# POE_V3.net
KiCad netlist of a schematic drawn in EAGLE
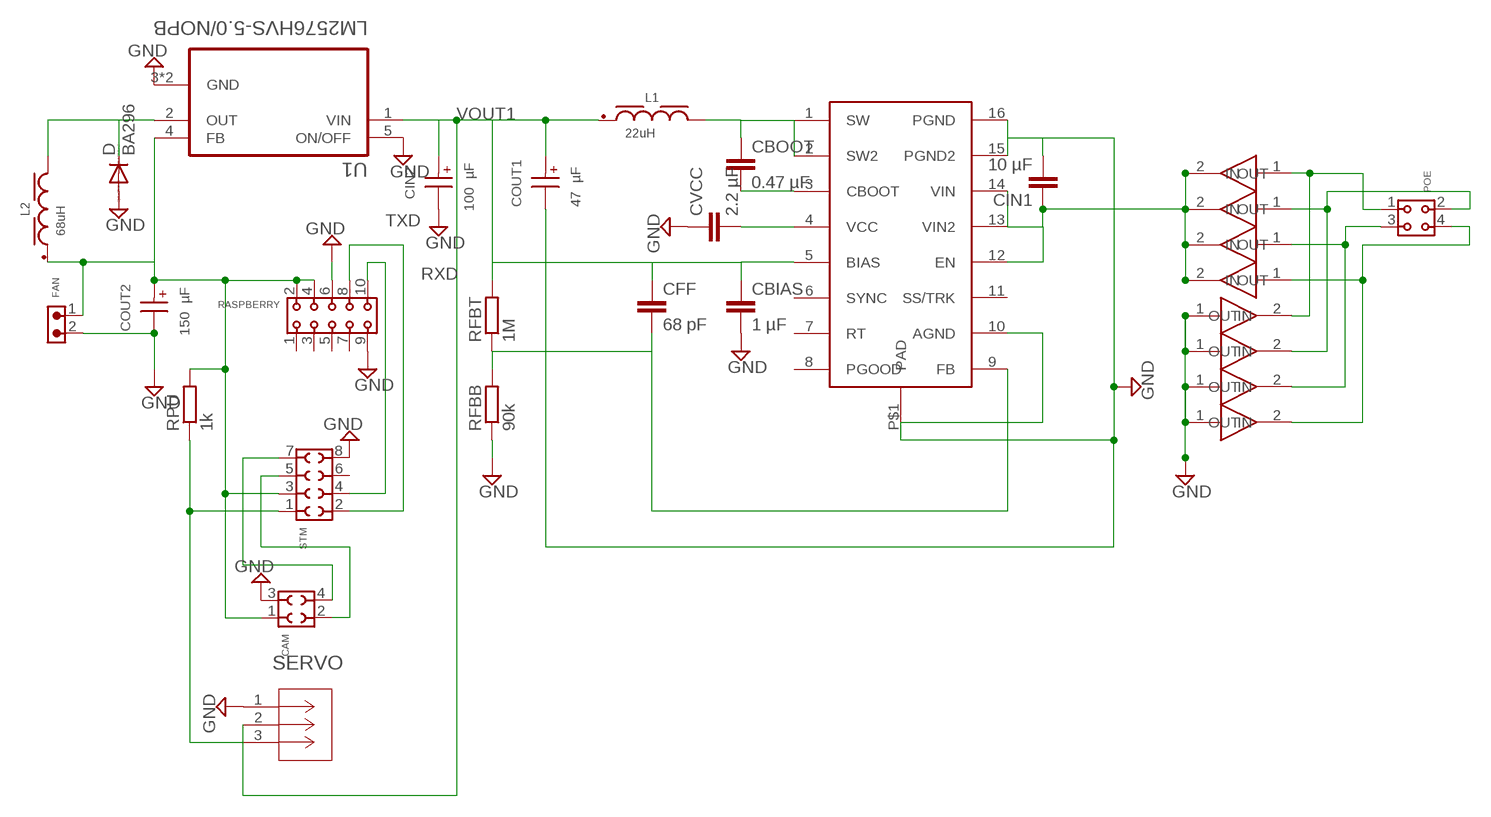
[diagram p0: schematic, sheet 1]

(export (version "E")
  (design (tool "Eeschema 10.0.6"))
  (components
    (comp (ref "CAM")
      (value "6100XX21821_61000421821")
      (footprint "eagle-import:61000421821")
      (libsource (lib "eagle-import") (part "6100XX21821_61000421821"))
    )
    (comp (ref "CBIAS")
      (value "1 µF")
      (footprint "eagle-import:C1206")
      (libsource (lib "eagle-import") (part "C-EUC1206"))
    )
    (comp (ref "CBOOT")
      (value "0.47 µF")
      (footprint "eagle-import:C1206")
      (libsource (lib "eagle-import") (part "C-EUC1206"))
    )
    (comp (ref "CFF")
      (value "68 pF")
      (footprint "eagle-import:C1206")
      (libsource (lib "eagle-import") (part "C-EUC1206"))
    )
    (comp (ref "CIN1")
      (value "10 µF")
      (footprint "eagle-import:C2220K")
      (libsource (lib "eagle-import") (part "rcl_334_C-EUC2220K"))
    )
    (comp (ref "CIN2")
      (value "100 µF")
      (footprint "eagle-import:WCAP-ASLI_6.3X5.5(DXL)")
      (libsource (lib "eagle-import") (part "WCAP-ASLI_6.3X5.5_865080343009"))
    )
    (comp (ref "COUT1")
      (value "47 µF")
      (footprint "eagle-import:WCAP-ASLI_5X5.5(DXL)")
      (libsource (lib "eagle-import") (part "WCAP-ASLI_5X5.5_865080342006"))
    )
    (comp (ref "COUT2")
      (value "150 µF")
      (footprint "eagle-import:WCAP-ASLI_6.3X5.5(DXL)")
      (libsource (lib "eagle-import") (part "WCAP-ASLI_6.3X5.5_865080143008"))
    )
    (comp (ref "CVCC")
      (value "2.2 µF")
      (footprint "eagle-import:C1206")
      (libsource (lib "eagle-import") (part "C-EUC1206"))
    )
    (comp (ref "D")
      (value "BA296")
      (footprint "eagle-import:P2-15")
      (libsource (lib "eagle-import") (part "BA296"))
    )
    (comp (ref "FAN")
      (value "6130XX11021_61300211021")
      (footprint "eagle-import:61300211021")
      (libsource (lib "eagle-import") (part "6130XX11021_61300211021"))
    )
    (comp (ref "L1")
      (value "22uH")
      (footprint "eagle-import:WE-PD_1260")
      (libsource (lib "eagle-import") (part "WE-PD_1260_744771122"))
    )
    (comp (ref "L2")
      (value "68uH")
      (footprint "eagle-import:WE-PD_1210")
      (libsource (lib "eagle-import") (part "WE-PD_1210_7447709680"))
    )
    (comp (ref "POE")
      (value "6130XX21821_61300421821")
      (footprint "eagle-import:61300421821")
      (libsource (lib "eagle-import") (part "6130XX21821_61300421821"))
    )
    (comp (ref "RASPBERRY")
      (value "6130XX21821_61301021821")
      (footprint "eagle-import:61301021821")
      (libsource (lib "eagle-import") (part "6130XX21821_61301021821"))
    )
    (comp (ref "RFBB")
      (value "90k")
      (footprint "eagle-import:M1206")
      (libsource (lib "eagle-import") (part "R-EU_M1206"))
    )
    (comp (ref "RFBT")
      (value "1M")
      (footprint "eagle-import:M1206")
      (libsource (lib "eagle-import") (part "R-EU_M1206"))
    )
    (comp (ref "RPU")
      (value "1k")
      (footprint "eagle-import:M1206")
      (libsource (lib "eagle-import") (part "R-EU_M1206"))
    )
    (comp (ref "SERVO")
      (value "22035035")
      (footprint "eagle-import:CON_22035035")
      (fields (field (name "COPYRIGHT") "Copyright (C) 2018 Accelerated Designs. All rights reserved"))
      (libsource (lib "eagle-import") (part "22035035"))
    )
    (comp (ref "STM")
      (value "6100XX21821_61000821821")
      (footprint "eagle-import:61000821821")
      (libsource (lib "eagle-import") (part "6100XX21821_61000821821"))
    )
    (comp (ref "U$1")
      (value "LM46002")
      (footprint "eagle-import:TSSOP16")
      (libsource (lib "eagle-import") (part "LM46002"))
    )
    (comp (ref "U$2")
      (value "RGF1D")
      (footprint "eagle-import:RGF1D")
      (libsource (lib "eagle-import") (part "RGF1D"))
    )
    (comp (ref "U$3")
      (value "RGF1D")
      (footprint "eagle-import:RGF1D")
      (libsource (lib "eagle-import") (part "RGF1D"))
    )
    (comp (ref "U$4")
      (value "RGF1D")
      (footprint "eagle-import:RGF1D")
      (libsource (lib "eagle-import") (part "RGF1D"))
    )
    (comp (ref "U$5")
      (value "RGF1D")
      (footprint "eagle-import:RGF1D")
      (libsource (lib "eagle-import") (part "RGF1D"))
    )
    (comp (ref "U$6")
      (value "RGF1D")
      (footprint "eagle-import:RGF1D")
      (libsource (lib "eagle-import") (part "RGF1D"))
    )
    (comp (ref "U$7")
      (value "RGF1D")
      (footprint "eagle-import:RGF1D")
      (libsource (lib "eagle-import") (part "RGF1D"))
    )
    (comp (ref "U$8")
      (value "RGF1D")
      (footprint "eagle-import:RGF1D")
      (libsource (lib "eagle-import") (part "RGF1D"))
    )
    (comp (ref "U$9")
      (value "RGF1D")
      (footprint "eagle-import:RGF1D")
      (libsource (lib "eagle-import") (part "RGF1D"))
    )
    (comp (ref "U1")
      (value "LM2576HVS-5.0/NOPB")
      (footprint "eagle-import:VREG_TPS79625KTTR")
      (fields
        (field (name "DIGI-KEY_PART_NUMBER") "LM2576HVS-5.0/NOPB-ND")
        (field (name "MF") "Texas Instruments")
      )
      (libsource (lib "eagle-import") (part "LM2576HVS-5.0/NOPB"))
    )
  )
  (nets
    (net (code "1") (name "/RXD") (class "Default")
      (node (ref "RASPBERRY") (pin "10") (pinfunction "10_10") (pintype "passive"))
      (node (ref "STM") (pin "4") (pinfunction "4_4") (pintype "passive"))
    )
    (net (code "2") (name "/TXD") (class "Default")
      (node (ref "RASPBERRY") (pin "8") (pinfunction "8_8") (pintype "passive"))
      (node (ref "STM") (pin "2") (pinfunction "2_2") (pintype "passive"))
    )
    (net (code "3") (name "/VOUT1") (class "Default")
      (node (ref "CBIAS") (pin "1") (pinfunction "1_1") (pintype "passive"))
      (node (ref "CFF") (pin "1") (pinfunction "1_1") (pintype "passive"))
      (node (ref "CIN2") (pin "1") (pinfunction "+_1") (pintype "passive"))
      (node (ref "COUT1") (pin "1") (pinfunction "+_1") (pintype "passive"))
      (node (ref "L1") (pin "1") (pinfunction "1_1") (pintype "passive"))
      (node (ref "RFBT") (pin "2") (pinfunction "2_2") (pintype "passive"))
      (node (ref "SERVO") (pin "2") (pinfunction "2_2") (pintype "passive"))
      (node (ref "U$1") (pin "5") (pinfunction "BIAS_5") (pintype "bidirectional"))
      (node (ref "U1") (pin "1") (pinfunction "VIN_1") (pintype "input"))
    )
    (net (code "4") (name "GND") (class "Default")
      (node (ref "CAM") (pin "3") (pinfunction "3_3") (pintype "passive"))
      (node (ref "CBIAS") (pin "2") (pinfunction "2_2") (pintype "passive"))
      (node (ref "CIN1") (pin "2") (pinfunction "2_2") (pintype "passive"))
      (node (ref "CIN2") (pin "2") (pinfunction "-_2") (pintype "passive"))
      (node (ref "COUT1") (pin "2") (pinfunction "-_2") (pintype "passive"))
      (node (ref "COUT2") (pin "2") (pinfunction "-_2") (pintype "passive"))
      (node (ref "CVCC") (pin "1") (pinfunction "1_1") (pintype "passive"))
      (node (ref "D") (pin "A") (pinfunction "A_A") (pintype "passive"))
      (node (ref "FAN") (pin "2") (pinfunction "2_2") (pintype "passive"))
      (node (ref "RASPBERRY") (pin "6") (pinfunction "6_6") (pintype "passive"))
      (node (ref "RASPBERRY") (pin "9") (pinfunction "9_9") (pintype "passive"))
      (node (ref "RFBB") (pin "1") (pinfunction "1_1") (pintype "passive"))
      (node (ref "SERVO") (pin "1") (pinfunction "1_1") (pintype "passive"))
      (node (ref "STM") (pin "8") (pinfunction "8_8") (pintype "passive"))
      (node (ref "U$1") (pin "10") (pinfunction "AGND_10") (pintype "bidirectional"))
      (node (ref "U$1") (pin "15") (pinfunction "PGND2_15") (pintype "bidirectional"))
      (node (ref "U$1") (pin "16") (pinfunction "PGND_16") (pintype "bidirectional"))
      (node (ref "U$1") (pin "P$1") (pinfunction "PAD_P$1") (pintype "bidirectional"))
      (node (ref "U$4") (pin "1") (pinfunction "IN_1") (pintype "bidirectional"))
      (node (ref "U$5") (pin "1") (pinfunction "IN_1") (pintype "bidirectional"))
      (node (ref "U$8") (pin "1") (pinfunction "IN_1") (pintype "bidirectional"))
      (node (ref "U$9") (pin "1") (pinfunction "IN_1") (pintype "bidirectional"))
      (node (ref "U1") (pin "3") (pinfunction "GND_3") (pintype "power_in"))
      (node (ref "U1") (pin "5") (pinfunction "ON/OFF_5") (pintype "input"))
      (node (ref "U1") (pin "6") (pinfunction "GND_6") (pintype "power_in"))
    )
    (net (code "5") (name "Net-(CAM-Pad2)") (class "Default")
      (node (ref "CAM") (pin "2") (pinfunction "2_2") (pintype "passive"))
      (node (ref "STM") (pin "5") (pinfunction "5_5") (pintype "passive"))
    )
    (net (code "6") (name "Net-(CAM-Pad4)") (class "Default")
      (node (ref "CAM") (pin "4") (pinfunction "4_4") (pintype "passive"))
      (node (ref "STM") (pin "7") (pinfunction "7_7") (pintype "passive"))
    )
    (net (code "7") (name "Net-(COUT2-+)") (class "Default")
      (node (ref "CAM") (pin "1") (pinfunction "1_1") (pintype "passive"))
      (node (ref "COUT2") (pin "1") (pinfunction "+_1") (pintype "passive"))
      (node (ref "FAN") (pin "1") (pinfunction "1_1") (pintype "passive"))
      (node (ref "L2") (pin "1") (pinfunction "1_1") (pintype "passive"))
      (node (ref "RASPBERRY") (pin "2") (pinfunction "2_2") (pintype "passive"))
      (node (ref "RASPBERRY") (pin "4") (pinfunction "4_4") (pintype "passive"))
      (node (ref "RPU") (pin "2") (pinfunction "2_2") (pintype "passive"))
      (node (ref "STM") (pin "3") (pinfunction "3_3") (pintype "passive"))
      (node (ref "U1") (pin "4") (pinfunction "FB_4") (pintype "output"))
    )
    (net (code "8") (name "Net-(RPU-Pad1)") (class "Default")
      (node (ref "RPU") (pin "1") (pinfunction "1_1") (pintype "passive"))
      (node (ref "SERVO") (pin "3") (pinfunction "3_3") (pintype "passive"))
      (node (ref "STM") (pin "1") (pinfunction "1_1") (pintype "passive"))
    )
    (net (code "9") (name "Net-(U$1-CBOOT)") (class "Default")
      (node (ref "CBOOT") (pin "2") (pinfunction "2_2") (pintype "passive"))
      (node (ref "U$1") (pin "3") (pinfunction "CBOOT_3") (pintype "bidirectional"))
    )
    (net (code "10") (name "Net-(U$1-EN)") (class "Default")
      (node (ref "CIN1") (pin "1") (pinfunction "1_1") (pintype "passive"))
      (node (ref "U$1") (pin "12") (pinfunction "EN_12") (pintype "bidirectional"))
      (node (ref "U$1") (pin "13") (pinfunction "VIN2_13") (pintype "bidirectional"))
      (node (ref "U$1") (pin "14") (pinfunction "VIN_14") (pintype "bidirectional"))
      (node (ref "U$2") (pin "2") (pinfunction "OUT_2") (pintype "bidirectional"))
      (node (ref "U$3") (pin "2") (pinfunction "OUT_2") (pintype "bidirectional"))
      (node (ref "U$6") (pin "2") (pinfunction "OUT_2") (pintype "bidirectional"))
      (node (ref "U$7") (pin "2") (pinfunction "OUT_2") (pintype "bidirectional"))
    )
    (net (code "11") (name "Net-(U$1-FB)") (class "Default")
      (node (ref "CFF") (pin "2") (pinfunction "2_2") (pintype "passive"))
      (node (ref "RFBB") (pin "2") (pinfunction "2_2") (pintype "passive"))
      (node (ref "RFBT") (pin "1") (pinfunction "1_1") (pintype "passive"))
      (node (ref "U$1") (pin "9") (pinfunction "FB_9") (pintype "bidirectional"))
    )
    (net (code "12") (name "Net-(U$1-SW)") (class "Default")
      (node (ref "CBOOT") (pin "1") (pinfunction "1_1") (pintype "passive"))
      (node (ref "L1") (pin "2") (pinfunction "2_2") (pintype "passive"))
      (node (ref "U$1") (pin "1") (pinfunction "SW_1") (pintype "bidirectional"))
      (node (ref "U$1") (pin "2") (pinfunction "SW2_2") (pintype "bidirectional"))
    )
    (net (code "13") (name "Net-(U$1-VCC)") (class "Default")
      (node (ref "CVCC") (pin "2") (pinfunction "2_2") (pintype "passive"))
      (node (ref "U$1") (pin "4") (pinfunction "VCC_4") (pintype "bidirectional"))
    )
    (net (code "14") (name "Net-(U$2-IN)") (class "Default")
      (node (ref "POE") (pin "1") (pinfunction "1_1") (pintype "passive"))
      (node (ref "U$2") (pin "1") (pinfunction "IN_1") (pintype "bidirectional"))
      (node (ref "U$4") (pin "2") (pinfunction "OUT_2") (pintype "bidirectional"))
    )
    (net (code "15") (name "Net-(U$3-IN)") (class "Default")
      (node (ref "POE") (pin "2") (pinfunction "2_2") (pintype "passive"))
      (node (ref "U$3") (pin "1") (pinfunction "IN_1") (pintype "bidirectional"))
      (node (ref "U$5") (pin "2") (pinfunction "OUT_2") (pintype "bidirectional"))
    )
    (net (code "16") (name "Net-(U$6-IN)") (class "Default")
      (node (ref "POE") (pin "3") (pinfunction "3_3") (pintype "passive"))
      (node (ref "U$6") (pin "1") (pinfunction "IN_1") (pintype "bidirectional"))
      (node (ref "U$8") (pin "2") (pinfunction "OUT_2") (pintype "bidirectional"))
    )
    (net (code "17") (name "Net-(U$7-IN)") (class "Default")
      (node (ref "POE") (pin "4") (pinfunction "4_4") (pintype "passive"))
      (node (ref "U$7") (pin "1") (pinfunction "IN_1") (pintype "bidirectional"))
      (node (ref "U$9") (pin "2") (pinfunction "OUT_2") (pintype "bidirectional"))
    )
    (net (code "18") (name "Net-(U1-OUT)") (class "Default")
      (node (ref "D") (pin "C") (pinfunction "C_C") (pintype "passive"))
      (node (ref "L2") (pin "2") (pinfunction "2_2") (pintype "passive"))
      (node (ref "U1") (pin "2") (pinfunction "OUT_2") (pintype "output"))
    )
    (net (code "19") (name "unconnected-(RASPBERRY-Pad1)") (class "Default")
      (node (ref "RASPBERRY") (pin "1") (pinfunction "1_1") (pintype "passive"))
    )
    (net (code "20") (name "unconnected-(RASPBERRY-Pad3)") (class "Default")
      (node (ref "RASPBERRY") (pin "3") (pinfunction "3_3") (pintype "passive"))
    )
    (net (code "21") (name "unconnected-(RASPBERRY-Pad5)") (class "Default")
      (node (ref "RASPBERRY") (pin "5") (pinfunction "5_5") (pintype "passive"))
    )
    (net (code "22") (name "unconnected-(RASPBERRY-Pad7)") (class "Default")
      (node (ref "RASPBERRY") (pin "7") (pinfunction "7_7") (pintype "passive"))
    )
    (net (code "23") (name "unconnected-(STM-Pad6)") (class "Default")
      (node (ref "STM") (pin "6") (pinfunction "6_6") (pintype "passive"))
    )
    (net (code "24") (name "unconnected-(U$1-PGOOD-Pad8)") (class "Default")
      (node (ref "U$1") (pin "8") (pinfunction "PGOOD_8") (pintype "bidirectional"))
    )
    (net (code "25") (name "unconnected-(U$1-RT-Pad7)") (class "Default")
      (node (ref "U$1") (pin "7") (pinfunction "RT_7") (pintype "bidirectional"))
    )
    (net (code "26") (name "unconnected-(U$1-SS{slash}TRK-Pad11)") (class "Default")
      (node (ref "U$1") (pin "11") (pinfunction "SS/TRK_11") (pintype "bidirectional"))
    )
    (net (code "27") (name "unconnected-(U$1-SYNC-Pad6)") (class "Default")
      (node (ref "U$1") (pin "6") (pinfunction "SYNC_6") (pintype "bidirectional"))
    )
  )
)
